# Arduino_Electronic_Load_Ver04.net
KiCad netlist of a schematic drawn in EAGLE
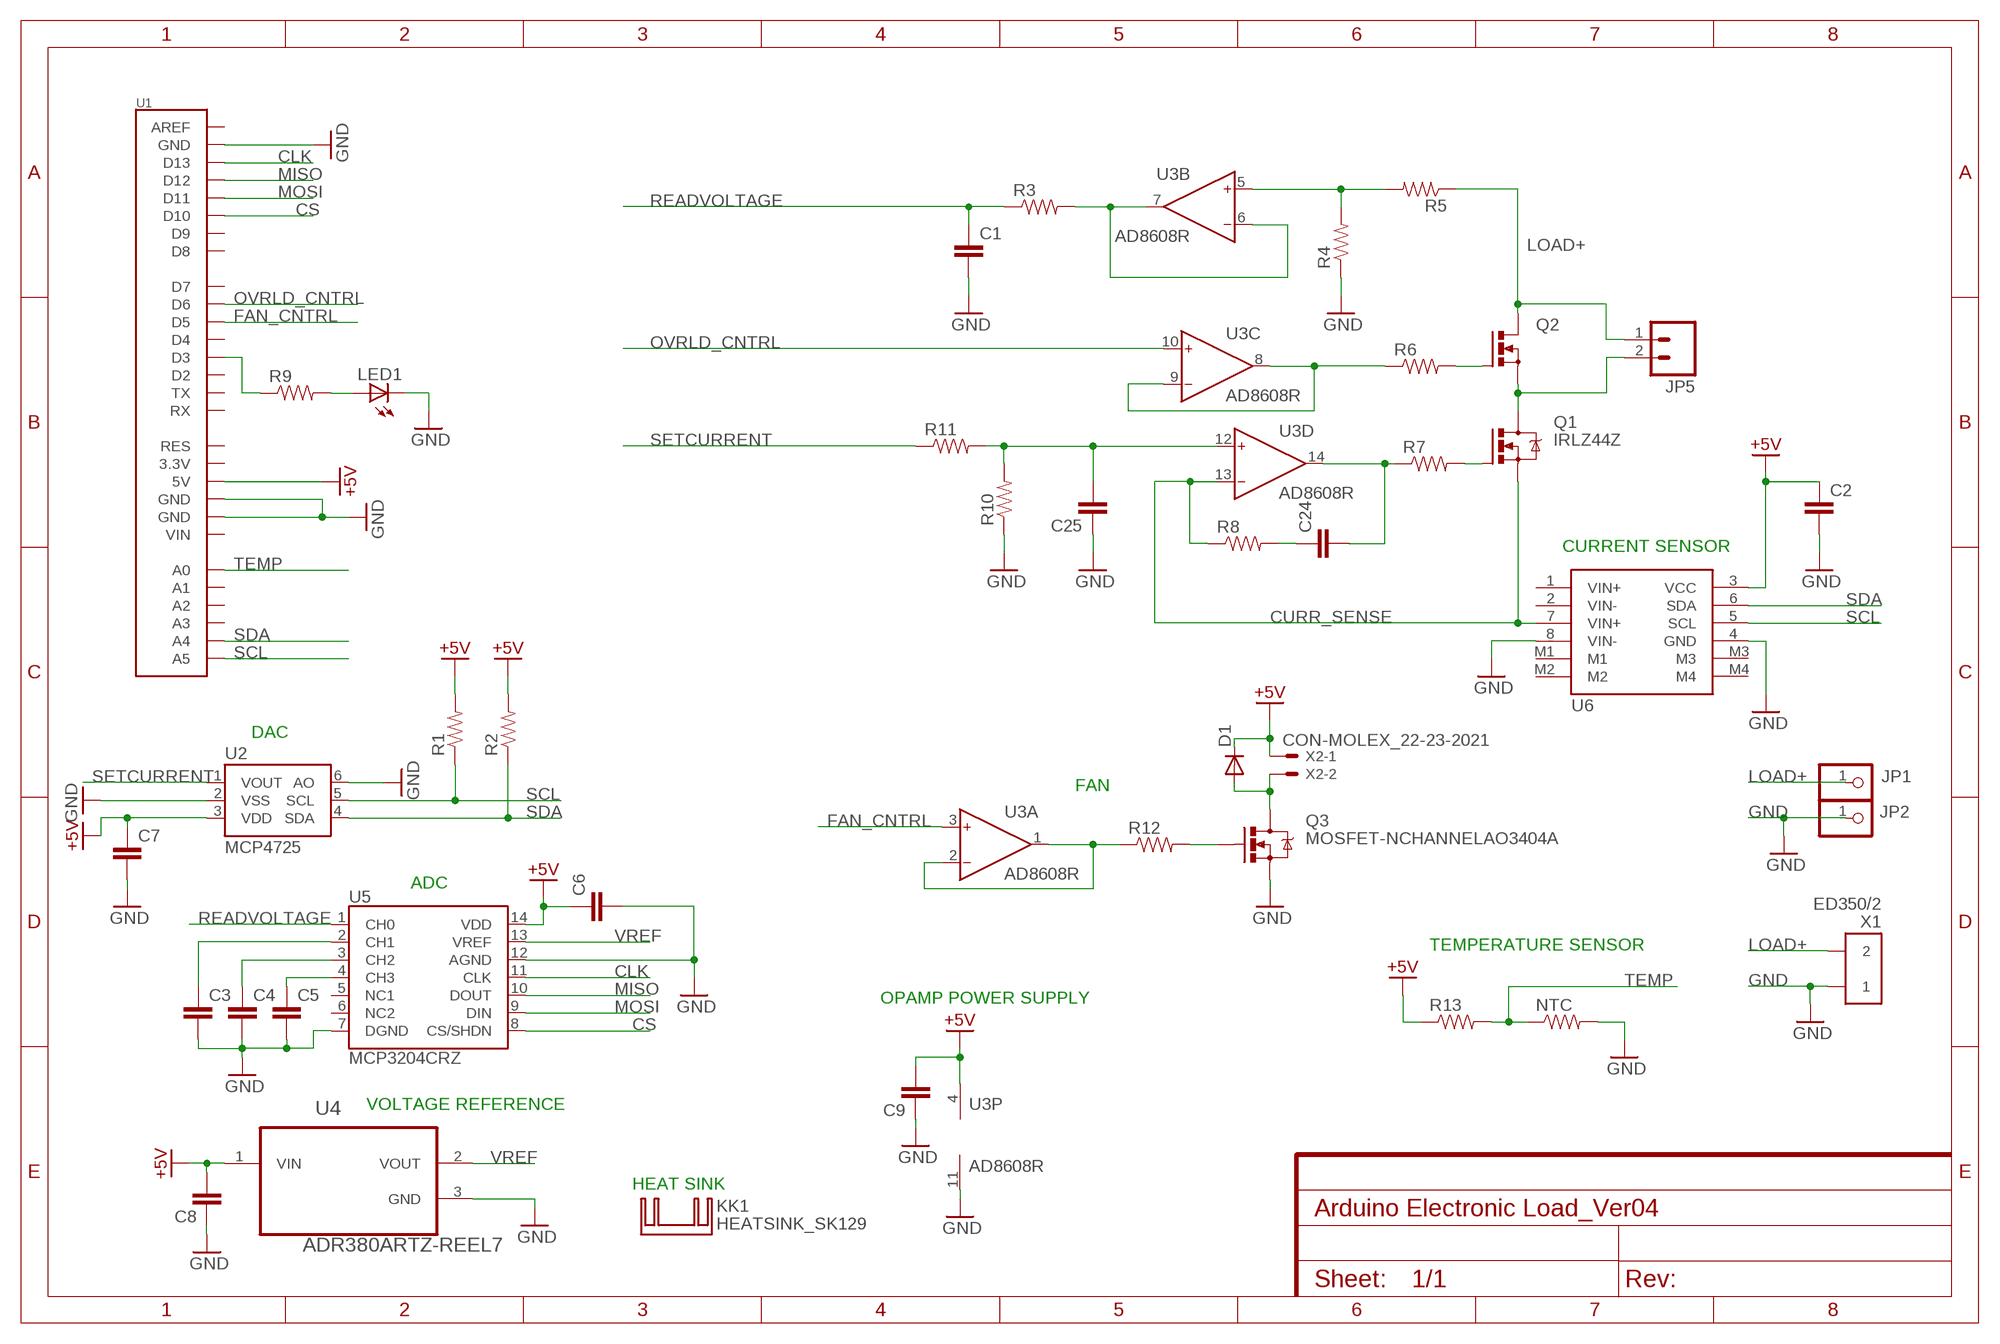
[diagram p0: schematic, sheet 1]

(export (version "E")
  (design (tool "Eeschema 10.0.6"))
  (components
    (comp (ref "C1")
      (value "CAP0603-CAP")
      (footprint "eagle-import:0603-CAP")
      (libsource (lib "eagle-import") (part "CAP0603-CAP"))
    )
    (comp (ref "C2")
      (value "CAP0603-CAP")
      (footprint "eagle-import:0603-CAP")
      (libsource (lib "eagle-import") (part "CAP0603-CAP"))
    )
    (comp (ref "C3")
      (value "CAP0603-CAP")
      (footprint "eagle-import:0603-CAP")
      (libsource (lib "eagle-import") (part "CAP0603-CAP"))
    )
    (comp (ref "C4")
      (value "CAP0603-CAP")
      (footprint "eagle-import:0603-CAP")
      (libsource (lib "eagle-import") (part "CAP0603-CAP"))
    )
    (comp (ref "C5")
      (value "CAP0603-CAP")
      (footprint "eagle-import:0603-CAP")
      (libsource (lib "eagle-import") (part "CAP0603-CAP"))
    )
    (comp (ref "C6")
      (value "CAP0603-CAP")
      (footprint "eagle-import:0603-CAP")
      (libsource (lib "eagle-import") (part "CAP0603-CAP"))
    )
    (comp (ref "C7")
      (value "CAP0603-CAP")
      (footprint "eagle-import:0603-CAP")
      (libsource (lib "eagle-import") (part "CAP0603-CAP"))
    )
    (comp (ref "C8")
      (value "CAP0603-CAP")
      (footprint "eagle-import:0603-CAP")
      (libsource (lib "eagle-import") (part "CAP0603-CAP"))
    )
    (comp (ref "C9")
      (value "CAP0603-CAP")
      (footprint "eagle-import:0603-CAP")
      (libsource (lib "eagle-import") (part "CAP0603-CAP"))
    )
    (comp (ref "C24")
      (value "CAP0603-CAP")
      (footprint "eagle-import:0603-CAP")
      (libsource (lib "eagle-import") (part "CAP0603-CAP"))
    )
    (comp (ref "C25")
      (value "CAP0603-CAP")
      (footprint "eagle-import:0603-CAP")
      (libsource (lib "eagle-import") (part "CAP0603-CAP"))
    )
    (comp (ref "D1")
      (value "DIODEPTH")
      (footprint "eagle-import:DIODE-1N4001")
      (libsource (lib "eagle-import") (part "DIODEPTH"))
    )
    (comp (ref "JP1")
      (value "PINHEAD_PINHD-1X1")
      (footprint "eagle-import:PINHEAD_1X01")
      (libsource (lib "eagle-import") (part "PINHEAD_PINHD-1X1"))
    )
    (comp (ref "JP2")
      (value "PINHEAD_PINHD-1X1")
      (footprint "eagle-import:PINHEAD_1X01")
      (libsource (lib "eagle-import") (part "PINHEAD_PINHD-1X1"))
    )
    (comp (ref "JP5")
      (value "M02")
      (footprint "eagle-import:1X02_LONGPADS")
      (libsource (lib "eagle-import") (part "M02"))
    )
    (comp (ref "KK1")
      (value "HEATSINK_SK129")
      (footprint "eagle-import:HEATSINK_SK129-HOLE")
      (libsource (lib "eagle-import") (part "HEATSINK_SK129"))
    )
    (comp (ref "LED1")
      (value "LED5MM")
      (footprint "eagle-import:LED5MM")
      (libsource (lib "eagle-import") (part "LED5MM"))
    )
    (comp (ref "NTC")
      (value "RESISTOR0402-RES")
      (footprint "eagle-import:0402-RES")
      (libsource (lib "eagle-import") (part "RESISTOR0402-RES"))
    )
    (comp (ref "Q1")
      (value "IRLZ44Z")
      (footprint "eagle-import:TO220BV_1")
      (libsource (lib "eagle-import") (part "IRLZ44Z"))
    )
    (comp (ref "Q2")
      (value "PMOSFET_NTO220BV")
      (footprint "eagle-import:TO220BV")
      (libsource (lib "eagle-import") (part "PMOSFET_NTO220BV"))
    )
    (comp (ref "Q3")
      (value "MOSFET-NCHANNELAO3404A")
      (footprint "eagle-import:SOT23-3")
      (libsource (lib "eagle-import") (part "MOSFET-NCHANNELAO3404A"))
    )
    (comp (ref "R1")
      (value "RESISTOR0603-RES")
      (footprint "eagle-import:0603-RES")
      (libsource (lib "eagle-import") (part "RESISTOR0603-RES"))
    )
    (comp (ref "R2")
      (value "RESISTOR0603-RES")
      (footprint "eagle-import:0603-RES")
      (libsource (lib "eagle-import") (part "RESISTOR0603-RES"))
    )
    (comp (ref "R3")
      (value "RESISTOR0603-RES")
      (footprint "eagle-import:0603-RES")
      (libsource (lib "eagle-import") (part "RESISTOR0603-RES"))
    )
    (comp (ref "R4")
      (value "RESISTOR0603-RES")
      (footprint "eagle-import:0603-RES")
      (libsource (lib "eagle-import") (part "RESISTOR0603-RES"))
    )
    (comp (ref "R5")
      (value "RESISTOR0603-RES")
      (footprint "eagle-import:0603-RES")
      (libsource (lib "eagle-import") (part "RESISTOR0603-RES"))
    )
    (comp (ref "R6")
      (value "RESISTOR0603-RES")
      (footprint "eagle-import:0603-RES")
      (libsource (lib "eagle-import") (part "RESISTOR0603-RES"))
    )
    (comp (ref "R7")
      (value "RESISTOR0603-RES")
      (footprint "eagle-import:0603-RES")
      (libsource (lib "eagle-import") (part "RESISTOR0603-RES"))
    )
    (comp (ref "R8")
      (value "RESISTOR0603-RES")
      (footprint "eagle-import:0603-RES")
      (libsource (lib "eagle-import") (part "RESISTOR0603-RES"))
    )
    (comp (ref "R9")
      (value "RESISTOR0603-RES")
      (footprint "eagle-import:0603-RES")
      (libsource (lib "eagle-import") (part "RESISTOR0603-RES"))
    )
    (comp (ref "R10")
      (value "RESISTOR0603-RES")
      (footprint "eagle-import:0603-RES")
      (libsource (lib "eagle-import") (part "RESISTOR0603-RES"))
    )
    (comp (ref "R11")
      (value "RESISTOR0603-RES")
      (footprint "eagle-import:0603-RES")
      (libsource (lib "eagle-import") (part "RESISTOR0603-RES"))
    )
    (comp (ref "R12")
      (value "RESISTOR0603-RES")
      (footprint "eagle-import:0603-RES")
      (libsource (lib "eagle-import") (part "RESISTOR0603-RES"))
    )
    (comp (ref "R13")
      (value "RESISTOR0603-RES")
      (footprint "eagle-import:0603-RES")
      (libsource (lib "eagle-import") (part "RESISTOR0603-RES"))
    )
    (comp (ref "U1")
      (value "ARDUINO_SHIELD")
      (footprint "eagle-import:DUEMILANOVE_SHIELD")
      (libsource (lib "eagle-import") (part "ARDUINO_SHIELD"))
    )
    (comp (ref "U2")
      (value "MCP4725")
      (footprint "eagle-import:SOT23-6")
      (libsource (lib "eagle-import") (part "MCP4725SOT-23"))
    )
    (comp (ref "U3")
      (value "AD8608R")
      (footprint "eagle-import:SO14")
      (libsource (lib "eagle-import") (part "AD8608R"))
    )
    (comp (ref "U4")
      (value "ADR380ARTZ-REEL7")
      (footprint "eagle-import:SOT95P237X112-3N")
      (libsource (lib "eagle-import") (part "ADR380ARTZ-REEL7"))
    )
    (comp (ref "U5")
      (value "MCP3204CRZ")
      (footprint "eagle-import:SOIC-14")
      (libsource (lib "eagle-import") (part "MCP3204CRZ"))
    )
    (comp (ref "U6")
      (value "INA219")
      (footprint "eagle-import:INA219")
      (libsource (lib "eagle-import") (part "INA219"))
    )
    (comp (ref "X1")
      (value "ED350/2")
      (footprint "eagle-import:ED350_2")
      (libsource (lib "eagle-import") (part "ED350/2"))
    )
    (comp (ref "X2")
      (value "CON-MOLEX_22-23-2021")
      (footprint "eagle-import:CON-MOLEX_22-23-2021")
      (fields (field (name "MF") "MOLEX") (field (name "MPN") "22-23-2021"))
      (libsource (lib "eagle-import") (part "CON-MOLEX_22-23-2021"))
    )
  )
  (nets
    (net (code "1") (name "+5V") (class "Default")
      (node (ref "C2") (pin "1") (pinfunction "1_1") (pintype "passive"))
      (node (ref "C6") (pin "1") (pinfunction "1_1") (pintype "passive"))
      (node (ref "C7") (pin "1") (pinfunction "1_1") (pintype "passive"))
      (node (ref "C8") (pin "2") (pinfunction "2_2") (pintype "passive"))
      (node (ref "C9") (pin "2") (pinfunction "2_2") (pintype "passive"))
      (node (ref "D1") (pin "C") (pinfunction "C_C") (pintype "passive"))
      (node (ref "R1") (pin "2") (pinfunction "2_2") (pintype "passive"))
      (node (ref "R13") (pin "1") (pinfunction "1_1") (pintype "passive"))
      (node (ref "R2") (pin "2") (pinfunction "2_2") (pintype "passive"))
      (node (ref "U1") (pin "5V") (pinfunction "5V_5V") (pintype "bidirectional"))
      (node (ref "U2") (pin "3") (pinfunction "VDD_3") (pintype "bidirectional"))
      (node (ref "U3") (pin "4") (pinfunction "V+_4") (pintype "power_in"))
      (node (ref "U4") (pin "1") (pinfunction "VIN_1") (pintype "passive"))
      (node (ref "U5") (pin "14") (pinfunction "VDD_14") (pintype "bidirectional"))
      (node (ref "U6") (pin "3") (pinfunction "VCC_3") (pintype "bidirectional"))
      (node (ref "X2") (pin "1") (pinfunction "S_1") (pintype "passive"))
    )
    (net (code "2") (name "/CLK") (class "Default")
      (node (ref "U1") (pin "D13") (pinfunction "D13_D13") (pintype "bidirectional"))
      (node (ref "U5") (pin "11") (pinfunction "CLK_11") (pintype "bidirectional"))
    )
    (net (code "3") (name "/CS") (class "Default")
      (node (ref "U1") (pin "D10") (pinfunction "D10_D10") (pintype "bidirectional"))
      (node (ref "U5") (pin "8") (pinfunction "CS/SHDN_8") (pintype "bidirectional"))
    )
    (net (code "4") (name "/CURR_SENSE") (class "Default")
      (node (ref "Q1") (pin "S") (pinfunction "S_S") (pintype "passive"))
      (node (ref "R8") (pin "1") (pinfunction "1_1") (pintype "passive"))
      (node (ref "U3") (pin "13") (pinfunction "IN-_13") (pintype "input"))
      (node (ref "U6") (pin "7") (pinfunction "VIN+_7") (pintype "bidirectional"))
    )
    (net (code "5") (name "/FAN_CNTRL") (class "Default")
      (node (ref "U1") (pin "D5") (pinfunction "D5_D5") (pintype "bidirectional"))
      (node (ref "U3") (pin "3") (pinfunction "IN+_3") (pintype "input"))
    )
    (net (code "6") (name "/LOAD+") (class "Default")
      (node (ref "JP1") (pin "1") (pinfunction "1_1") (pintype "passive"))
      (node (ref "JP5") (pin "1") (pinfunction "1_1") (pintype "passive"))
      (node (ref "Q2") (pin "D") (pinfunction "D_D") (pintype "passive"))
      (node (ref "R5") (pin "1") (pinfunction "1_1") (pintype "passive"))
      (node (ref "X1") (pin "P$2") (pinfunction "2_P$2") (pintype "bidirectional"))
    )
    (net (code "7") (name "/MISO") (class "Default")
      (node (ref "U1") (pin "D12") (pinfunction "D12_D12") (pintype "bidirectional"))
      (node (ref "U5") (pin "10") (pinfunction "DOUT_10") (pintype "bidirectional"))
    )
    (net (code "8") (name "/MOSI") (class "Default")
      (node (ref "U1") (pin "D11") (pinfunction "D11_D11") (pintype "bidirectional"))
      (node (ref "U5") (pin "9") (pinfunction "DIN_9") (pintype "bidirectional"))
    )
    (net (code "9") (name "/OVRLD_CNTRL") (class "Default")
      (node (ref "U1") (pin "D6") (pinfunction "D6_D6") (pintype "bidirectional"))
      (node (ref "U3") (pin "10") (pinfunction "IN+_10") (pintype "input"))
    )
    (net (code "10") (name "/READVOLTAGE") (class "Default")
      (node (ref "C1") (pin "1") (pinfunction "1_1") (pintype "passive"))
      (node (ref "R3") (pin "1") (pinfunction "1_1") (pintype "passive"))
      (node (ref "U5") (pin "1") (pinfunction "CH0_1") (pintype "bidirectional"))
    )
    (net (code "11") (name "/SCL") (class "Default")
      (node (ref "R1") (pin "1") (pinfunction "1_1") (pintype "passive"))
      (node (ref "U1") (pin "A5") (pinfunction "A5_A5") (pintype "bidirectional"))
      (node (ref "U2") (pin "5") (pinfunction "SCL_5") (pintype "bidirectional"))
      (node (ref "U6") (pin "5") (pinfunction "SCL_5") (pintype "bidirectional"))
    )
    (net (code "12") (name "/SDA") (class "Default")
      (node (ref "R2") (pin "1") (pinfunction "1_1") (pintype "passive"))
      (node (ref "U1") (pin "A4") (pinfunction "A4_A4") (pintype "bidirectional"))
      (node (ref "U2") (pin "4") (pinfunction "SDA_4") (pintype "bidirectional"))
      (node (ref "U6") (pin "6") (pinfunction "SDA_6") (pintype "bidirectional"))
    )
    (net (code "13") (name "/SETCURRENT") (class "Default")
      (node (ref "R11") (pin "1") (pinfunction "1_1") (pintype "passive"))
      (node (ref "U2") (pin "1") (pinfunction "VOUT_1") (pintype "bidirectional"))
    )
    (net (code "14") (name "/TEMP") (class "Default")
      (node (ref "NTC") (pin "1") (pinfunction "1_1") (pintype "passive"))
      (node (ref "R13") (pin "2") (pinfunction "2_2") (pintype "passive"))
      (node (ref "U1") (pin "A0") (pinfunction "A0_A0") (pintype "bidirectional"))
    )
    (net (code "15") (name "/VREF") (class "Default")
      (node (ref "U4") (pin "2") (pinfunction "VOUT_2") (pintype "passive"))
      (node (ref "U5") (pin "13") (pinfunction "VREF_13") (pintype "bidirectional"))
    )
    (net (code "16") (name "GND") (class "Default")
      (node (ref "C1") (pin "2") (pinfunction "2_2") (pintype "passive"))
      (node (ref "C2") (pin "2") (pinfunction "2_2") (pintype "passive"))
      (node (ref "C25") (pin "1") (pinfunction "1_1") (pintype "passive"))
      (node (ref "C3") (pin "2") (pinfunction "2_2") (pintype "passive"))
      (node (ref "C4") (pin "2") (pinfunction "2_2") (pintype "passive"))
      (node (ref "C5") (pin "2") (pinfunction "2_2") (pintype "passive"))
      (node (ref "C6") (pin "2") (pinfunction "2_2") (pintype "passive"))
      (node (ref "C7") (pin "2") (pinfunction "2_2") (pintype "passive"))
      (node (ref "C8") (pin "1") (pinfunction "1_1") (pintype "passive"))
      (node (ref "C9") (pin "1") (pinfunction "1_1") (pintype "passive"))
      (node (ref "JP2") (pin "1") (pinfunction "1_1") (pintype "passive"))
      (node (ref "LED1") (pin "K") (pinfunction "C_K") (pintype "passive"))
      (node (ref "NTC") (pin "2") (pinfunction "2_2") (pintype "passive"))
      (node (ref "Q3") (pin "2") (pinfunction "S_2") (pintype "passive"))
      (node (ref "R10") (pin "1") (pinfunction "1_1") (pintype "passive"))
      (node (ref "R4") (pin "1") (pinfunction "1_1") (pintype "passive"))
      (node (ref "U1") (pin "GND@0") (pinfunction "GND_GND@0") (pintype "bidirectional"))
      (node (ref "U1") (pin "GND@1") (pinfunction "GND_GND@1") (pintype "bidirectional"))
      (node (ref "U1") (pin "GND@2") (pinfunction "GND_GND@2") (pintype "bidirectional"))
      (node (ref "U2") (pin "2") (pinfunction "VSS_2") (pintype "bidirectional"))
      (node (ref "U2") (pin "6") (pinfunction "AO_6") (pintype "bidirectional"))
      (node (ref "U3") (pin "11") (pinfunction "V-_11") (pintype "power_in"))
      (node (ref "U4") (pin "3") (pinfunction "GND_3") (pintype "passive"))
      (node (ref "U5") (pin "12") (pinfunction "AGND_12") (pintype "bidirectional"))
      (node (ref "U5") (pin "7") (pinfunction "DGND_7") (pintype "bidirectional"))
      (node (ref "U6") (pin "4") (pinfunction "GND_4") (pintype "bidirectional"))
      (node (ref "U6") (pin "8") (pinfunction "VIN-_8") (pintype "bidirectional"))
      (node (ref "X1") (pin "P$1") (pinfunction "1_P$1") (pintype "bidirectional"))
    )
    (net (code "17") (name "Net-(C24-Pad1)") (class "Default")
      (node (ref "C24") (pin "1") (pinfunction "1_1") (pintype "passive"))
      (node (ref "R8") (pin "2") (pinfunction "2_2") (pintype "passive"))
    )
    (net (code "18") (name "Net-(JP5-Pad2)") (class "Default")
      (node (ref "JP5") (pin "2") (pinfunction "2_2") (pintype "passive"))
      (node (ref "Q1") (pin "D") (pinfunction "D_D") (pintype "passive"))
      (node (ref "Q2") (pin "S") (pinfunction "S_S") (pintype "passive"))
    )
    (net (code "19") (name "Net-(LED1-PadA)") (class "Default")
      (node (ref "LED1") (pin "A") (pinfunction "A_A") (pintype "passive"))
      (node (ref "R9") (pin "2") (pinfunction "2_2") (pintype "passive"))
    )
    (net (code "20") (name "Net-(Q1-PadG)") (class "Default")
      (node (ref "Q1") (pin "G") (pinfunction "G_G") (pintype "passive"))
      (node (ref "R7") (pin "2") (pinfunction "2_2") (pintype "passive"))
    )
    (net (code "21") (name "Net-(Q2-PadG)") (class "Default")
      (node (ref "Q2") (pin "G") (pinfunction "G_G") (pintype "passive"))
      (node (ref "R6") (pin "2") (pinfunction "2_2") (pintype "passive"))
    )
    (net (code "22") (name "Net-(Q3-D)") (class "Default")
      (node (ref "D1") (pin "A") (pinfunction "A_A") (pintype "passive"))
      (node (ref "Q3") (pin "3") (pinfunction "D_3") (pintype "passive"))
      (node (ref "X2") (pin "2") (pinfunction "S_2") (pintype "passive"))
    )
    (net (code "23") (name "Net-(Q3-G)") (class "Default")
      (node (ref "Q3") (pin "1") (pinfunction "G_1") (pintype "passive"))
      (node (ref "R12") (pin "2") (pinfunction "2_2") (pintype "passive"))
    )
    (net (code "24") (name "Net-(R9-Pad1)") (class "Default")
      (node (ref "R9") (pin "1") (pinfunction "1_1") (pintype "passive"))
      (node (ref "U1") (pin "D3") (pinfunction "D3_D3") (pintype "bidirectional"))
    )
    (net (code "25") (name "Net-(U3A-IN-)") (class "Default")
      (node (ref "R12") (pin "1") (pinfunction "1_1") (pintype "passive"))
      (node (ref "U3") (pin "1") (pinfunction "OUT_1") (pintype "output"))
      (node (ref "U3") (pin "2") (pinfunction "IN-_2") (pintype "input"))
    )
    (net (code "26") (name "Net-(U3B-IN+)") (class "Default")
      (node (ref "R4") (pin "2") (pinfunction "2_2") (pintype "passive"))
      (node (ref "R5") (pin "2") (pinfunction "2_2") (pintype "passive"))
      (node (ref "U3") (pin "5") (pinfunction "IN+_5") (pintype "input"))
    )
    (net (code "27") (name "Net-(U3B-IN-)") (class "Default")
      (node (ref "R3") (pin "2") (pinfunction "2_2") (pintype "passive"))
      (node (ref "U3") (pin "6") (pinfunction "IN-_6") (pintype "input"))
      (node (ref "U3") (pin "7") (pinfunction "OUT_7") (pintype "output"))
    )
    (net (code "28") (name "Net-(U3C-IN-)") (class "Default")
      (node (ref "R6") (pin "1") (pinfunction "1_1") (pintype "passive"))
      (node (ref "U3") (pin "8") (pinfunction "OUT_8") (pintype "output"))
      (node (ref "U3") (pin "9") (pinfunction "IN-_9") (pintype "input"))
    )
    (net (code "29") (name "Net-(U3D-IN+)") (class "Default")
      (node (ref "C25") (pin "2") (pinfunction "2_2") (pintype "passive"))
      (node (ref "R10") (pin "2") (pinfunction "2_2") (pintype "passive"))
      (node (ref "R11") (pin "2") (pinfunction "2_2") (pintype "passive"))
      (node (ref "U3") (pin "12") (pinfunction "IN+_12") (pintype "input"))
    )
    (net (code "30") (name "Net-(U3D-OUT)") (class "Default")
      (node (ref "C24") (pin "2") (pinfunction "2_2") (pintype "passive"))
      (node (ref "R7") (pin "1") (pinfunction "1_1") (pintype "passive"))
      (node (ref "U3") (pin "14") (pinfunction "OUT_14") (pintype "output"))
    )
    (net (code "31") (name "Net-(U5-CH1)") (class "Default")
      (node (ref "C3") (pin "1") (pinfunction "1_1") (pintype "passive"))
      (node (ref "U5") (pin "2") (pinfunction "CH1_2") (pintype "bidirectional"))
    )
    (net (code "32") (name "Net-(U5-CH2)") (class "Default")
      (node (ref "C4") (pin "1") (pinfunction "1_1") (pintype "passive"))
      (node (ref "U5") (pin "3") (pinfunction "CH2_3") (pintype "bidirectional"))
    )
    (net (code "33") (name "Net-(U5-CH3)") (class "Default")
      (node (ref "C5") (pin "1") (pinfunction "1_1") (pintype "passive"))
      (node (ref "U5") (pin "4") (pinfunction "CH3_4") (pintype "bidirectional"))
    )
    (net (code "34") (name "unconnected-(U1-Pad3.3V)") (class "Default")
      (node (ref "U1") (pin "3.3V") (pinfunction "3.3V_3.3V") (pintype "bidirectional"))
    )
    (net (code "35") (name "unconnected-(U1-PadA1)") (class "Default")
      (node (ref "U1") (pin "A1") (pinfunction "A1_A1") (pintype "bidirectional"))
    )
    (net (code "36") (name "unconnected-(U1-PadA2)") (class "Default")
      (node (ref "U1") (pin "A2") (pinfunction "A2_A2") (pintype "bidirectional"))
    )
    (net (code "37") (name "unconnected-(U1-PadA3)") (class "Default")
      (node (ref "U1") (pin "A3") (pinfunction "A3_A3") (pintype "bidirectional"))
    )
    (net (code "38") (name "unconnected-(U1-PadAREF)") (class "Default")
      (node (ref "U1") (pin "AREF") (pinfunction "AREF_AREF") (pintype "bidirectional"))
    )
    (net (code "39") (name "unconnected-(U1-PadD2)") (class "Default")
      (node (ref "U1") (pin "D2") (pinfunction "D2_D2") (pintype "bidirectional"))
    )
    (net (code "40") (name "unconnected-(U1-PadD4)") (class "Default")
      (node (ref "U1") (pin "D4") (pinfunction "D4_D4") (pintype "bidirectional"))
    )
    (net (code "41") (name "unconnected-(U1-PadD7)") (class "Default")
      (node (ref "U1") (pin "D7") (pinfunction "D7_D7") (pintype "bidirectional"))
    )
    (net (code "42") (name "unconnected-(U1-PadD8)") (class "Default")
      (node (ref "U1") (pin "D8") (pinfunction "D8_D8") (pintype "bidirectional"))
    )
    (net (code "43") (name "unconnected-(U1-PadD9)") (class "Default")
      (node (ref "U1") (pin "D9") (pinfunction "D9_D9") (pintype "bidirectional"))
    )
    (net (code "44") (name "unconnected-(U1-PadRES)") (class "Default")
      (node (ref "U1") (pin "RES") (pinfunction "RES_RES") (pintype "bidirectional"))
    )
    (net (code "45") (name "unconnected-(U1-PadRX)") (class "Default")
      (node (ref "U1") (pin "RX") (pinfunction "RX_RX") (pintype "bidirectional"))
    )
    (net (code "46") (name "unconnected-(U1-PadTX)") (class "Default")
      (node (ref "U1") (pin "TX") (pinfunction "TX_TX") (pintype "bidirectional"))
    )
    (net (code "47") (name "unconnected-(U1-PadVIN)") (class "Default")
      (node (ref "U1") (pin "VIN") (pinfunction "VIN_VIN") (pintype "bidirectional"))
    )
    (net (code "48") (name "unconnected-(U5-NC1-Pad5)") (class "Default")
      (node (ref "U5") (pin "5") (pinfunction "NC1_5") (pintype "bidirectional"))
    )
    (net (code "49") (name "unconnected-(U5-NC2-Pad6)") (class "Default")
      (node (ref "U5") (pin "6") (pinfunction "NC2_6") (pintype "bidirectional"))
    )
    (net (code "50") (name "unconnected-(U6-PadM1)") (class "Default")
      (node (ref "U6") (pin "M1") (pinfunction "M1_M1") (pintype "bidirectional"))
    )
    (net (code "51") (name "unconnected-(U6-PadM2)") (class "Default")
      (node (ref "U6") (pin "M2") (pinfunction "M2_M2") (pintype "bidirectional"))
    )
    (net (code "52") (name "unconnected-(U6-PadM3)") (class "Default")
      (node (ref "U6") (pin "M3") (pinfunction "M3_M3") (pintype "bidirectional"))
    )
    (net (code "53") (name "unconnected-(U6-PadM4)") (class "Default")
      (node (ref "U6") (pin "M4") (pinfunction "M4_M4") (pintype "bidirectional"))
    )
    (net (code "54") (name "unconnected-(U6-VIN+-Pad1)") (class "Default")
      (node (ref "U6") (pin "1") (pinfunction "VIN+_1") (pintype "bidirectional"))
    )
    (net (code "55") (name "unconnected-(U6-VIN--Pad2)") (class "Default")
      (node (ref "U6") (pin "2") (pinfunction "VIN-_2") (pintype "bidirectional"))
    )
  )
)
